# schematic.net
KiCad netlist of a schematic drawn in Altium Designer
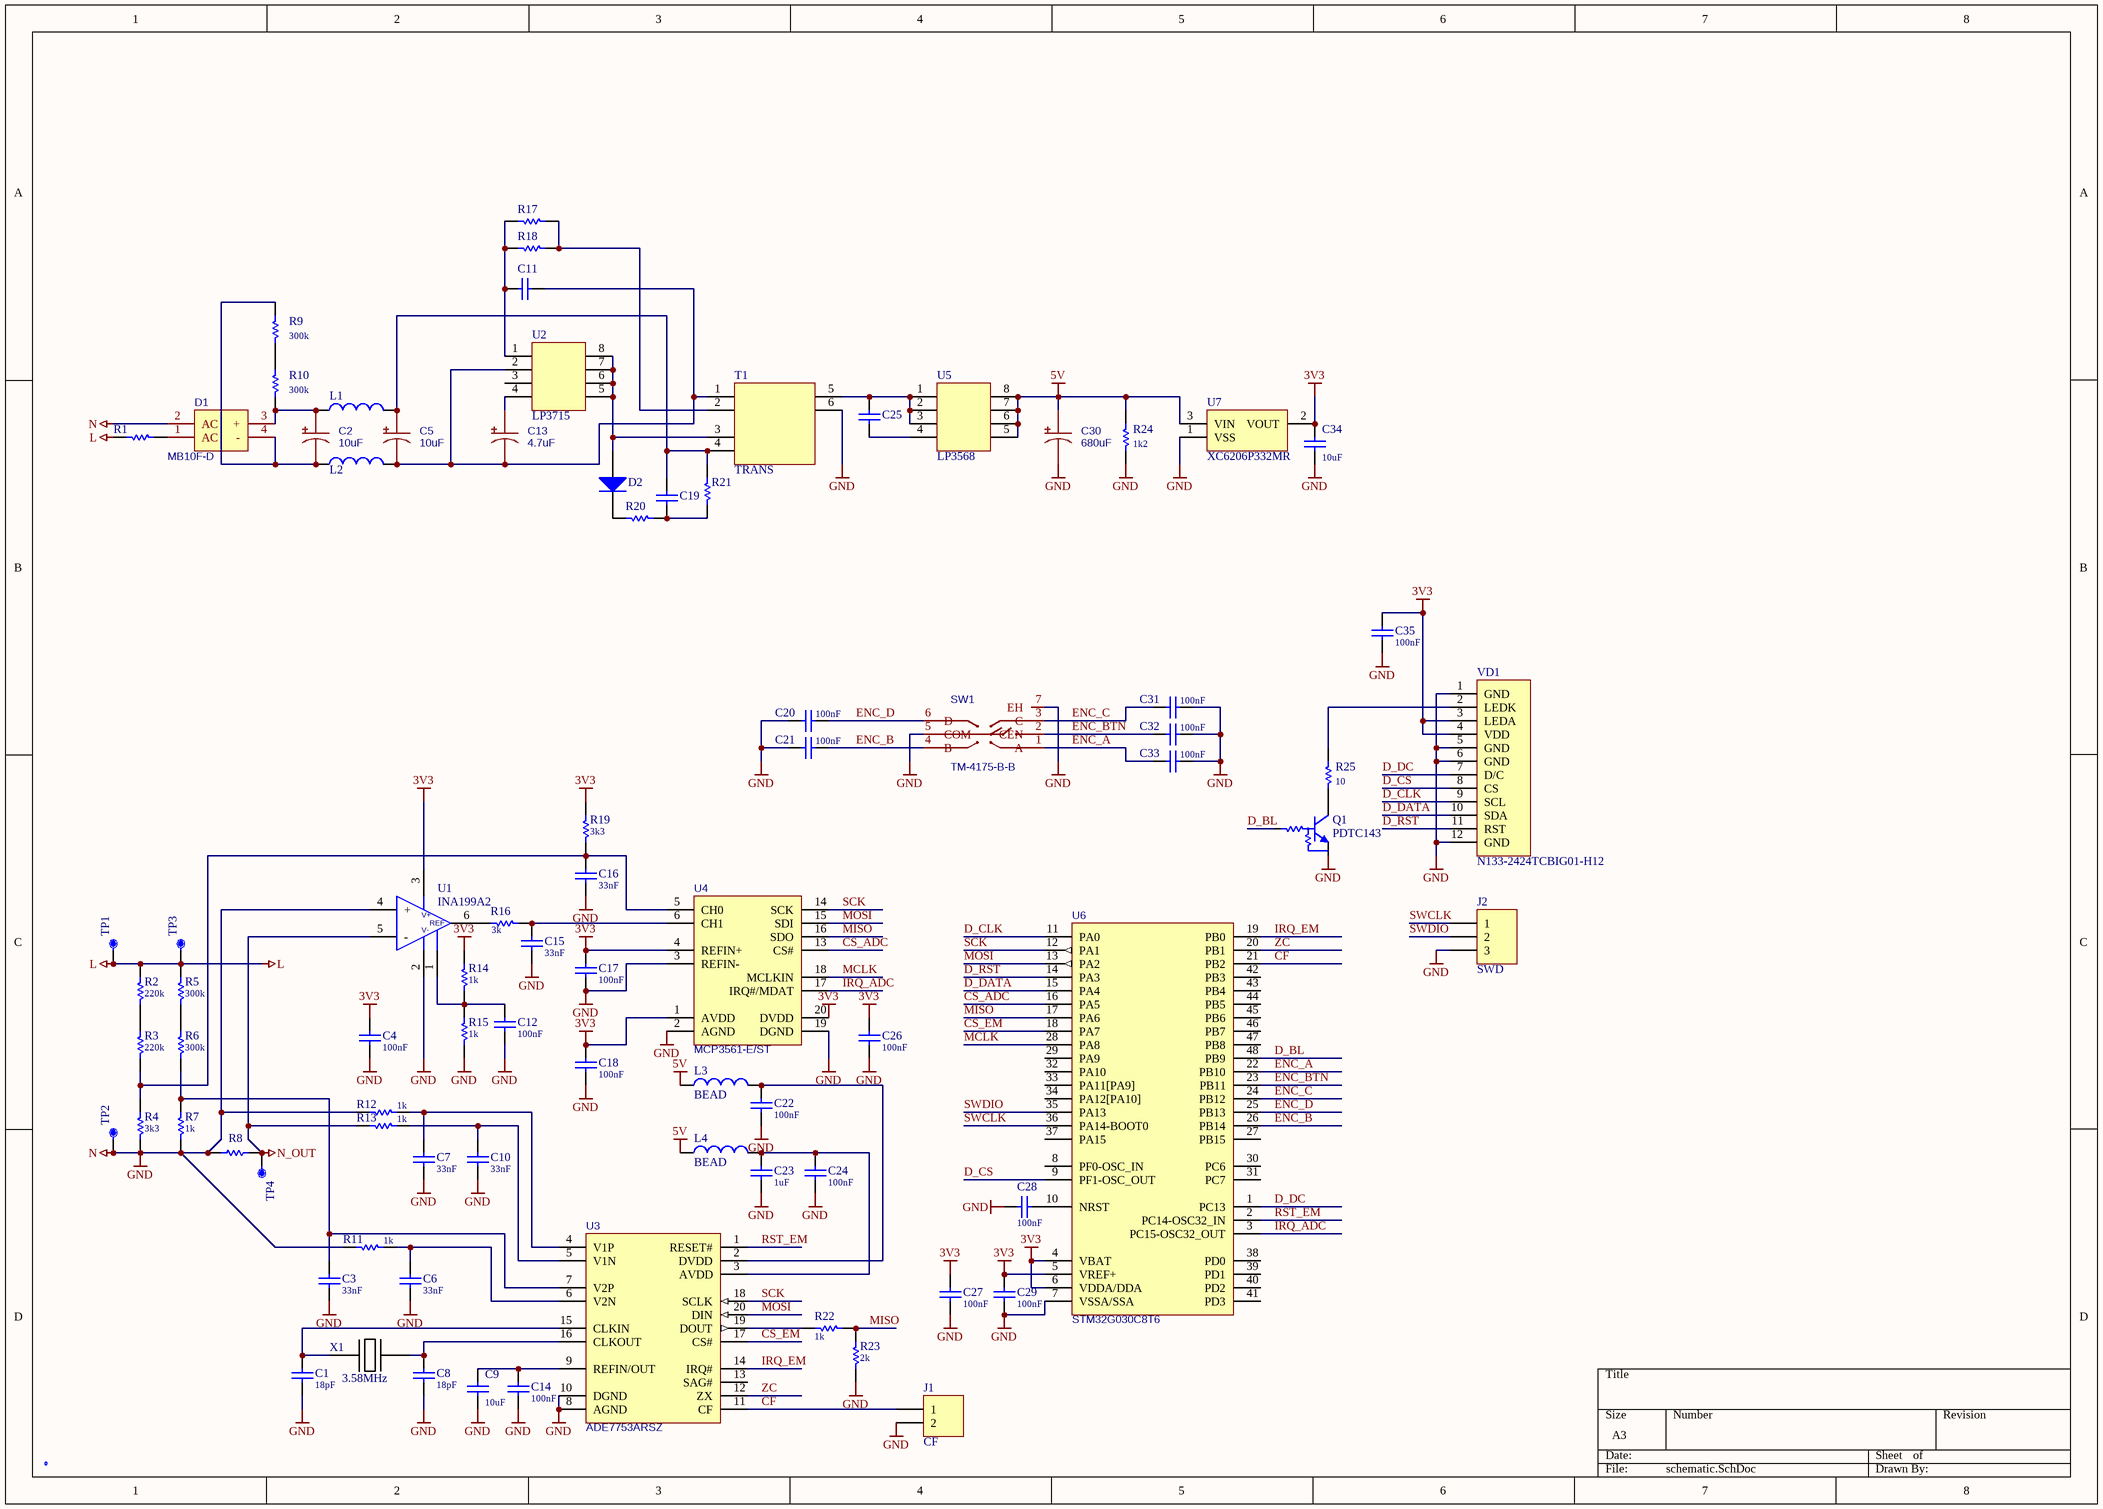
[diagram p0: schematic.SchDoc]

(export (version "E")
  (design (tool "Eeschema 10.0.6"))
  (components
    (comp (ref "C1")
      (value "18pF")
      (footprint "C0402")
      (fields (field (name "LCSC PART NUMBER") "C33149"))
      (libsource (lib "Miscellaneous Devices") (part "CAP"))
    )
    (comp (ref "C2")
      (value "10uF")
      (footprint "CAP-TH_BD8.0-P3.50-D0.6-FD_1")
      (description "01EC4138MHT10uF400V")
      (libsource (lib "altium-import") (part "root_0_220uF_"))
    )
    (comp (ref "C3")
      (value "33nF")
      (footprint "C0402")
      (libsource (lib "Miscellaneous Devices") (part "CAP"))
    )
    (comp (ref "C4")
      (value "100nF")
      (footprint "C0402")
      (libsource (lib "Miscellaneous Devices") (part "CAP"))
    )
    (comp (ref "C5")
      (value "10uF")
      (footprint "CAP-TH_BD8.0-P3.50-D0.6-FD_1")
      (description "01EC4138MHT10uF400V")
      (libsource (lib "altium-import") (part "root_0_220uF_"))
    )
    (comp (ref "C6")
      (value "33nF")
      (footprint "C0402")
      (libsource (lib "Miscellaneous Devices") (part "CAP"))
    )
    (comp (ref "C7")
      (value "33nF")
      (footprint "C0402")
      (fields (field (name "LCSC PART NUMBER") "C33149"))
      (libsource (lib "Miscellaneous Devices") (part "CAP"))
    )
    (comp (ref "C8")
      (value "18pF")
      (footprint "C0402")
      (fields (field (name "LCSC PART NUMBER") "C33149"))
      (libsource (lib "Miscellaneous Devices") (part "CAP"))
    )
    (comp (ref "C9")
      (value "10uF")
      (footprint "C1206")
      (libsource (lib "Miscellaneous Devices") (part "CAP"))
    )
    (comp (ref "C10")
      (value "33nF")
      (footprint "C0402")
      (fields (field (name "LCSC PART NUMBER") "C33149"))
      (libsource (lib "Miscellaneous Devices") (part "CAP"))
    )
    (comp (ref "C11") (value "~") (footprint "C0603") (libsource (lib "Miscellaneous Devices") (part "CAP")))
    (comp (ref "C12")
      (value "100nF")
      (footprint "C0402")
      (libsource (lib "Miscellaneous Devices") (part "CAP"))
    )
    (comp (ref "C13")
      (value "4.7uF")
      (footprint "CAP-TH_BD4.0-P2")
      (libsource (lib "altium-import") (part "root_0_220uF_"))
    )
    (comp (ref "C14")
      (value "100nF")
      (footprint "C0402")
      (libsource (lib "Miscellaneous Devices") (part "CAP"))
    )
    (comp (ref "C15")
      (value "33nF")
      (footprint "C0402")
      (libsource (lib "Miscellaneous Devices") (part "CAP"))
    )
    (comp (ref "C16")
      (value "33nF")
      (footprint "C0402")
      (libsource (lib "Miscellaneous Devices") (part "CAP"))
    )
    (comp (ref "C17")
      (value "100nF")
      (footprint "C0402")
      (libsource (lib "Miscellaneous Devices") (part "CAP"))
    )
    (comp (ref "C18")
      (value "100nF")
      (footprint "C0402")
      (libsource (lib "Miscellaneous Devices") (part "CAP"))
    )
    (comp (ref "C19") (value "~") (footprint "C1206") (libsource (lib "Miscellaneous Devices") (part "CAP")))
    (comp (ref "C20")
      (value "100nF")
      (footprint "C0402")
      (libsource (lib "Miscellaneous Devices") (part "CAP"))
    )
    (comp (ref "C21")
      (value "100nF")
      (footprint "C0402")
      (libsource (lib "Miscellaneous Devices") (part "CAP"))
    )
    (comp (ref "C22")
      (value "100nF")
      (footprint "C0402")
      (libsource (lib "Miscellaneous Devices") (part "CAP"))
    )
    (comp (ref "C23")
      (value "1uF")
      (footprint "C0603")
      (description "1uF 50V 0603")
      (fields (field (name "LCSC PART NUMBER") "C90540"))
      (libsource (lib "Miscellaneous Devices") (part "CAP"))
    )
    (comp (ref "C24")
      (value "100nF")
      (footprint "C0402")
      (libsource (lib "Miscellaneous Devices") (part "CAP"))
    )
    (comp (ref "C25") (value "~") (footprint "C0603") (libsource (lib "Miscellaneous Devices") (part "CAP")))
    (comp (ref "C26")
      (value "100nF")
      (footprint "C0402")
      (libsource (lib "Miscellaneous Devices") (part "CAP"))
    )
    (comp (ref "C27")
      (value "100nF")
      (footprint "C0402")
      (libsource (lib "Miscellaneous Devices") (part "CAP"))
    )
    (comp (ref "C28")
      (value "100nF")
      (footprint "C0603")
      (libsource (lib "Miscellaneous Devices") (part "CAP"))
    )
    (comp (ref "C29")
      (value "100nF")
      (footprint "C0402")
      (libsource (lib "Miscellaneous Devices") (part "CAP"))
    )
    (comp (ref "C30")
      (value "680uF")
      (footprint "CAP-TH_BD6.3-P2.54")
      (libsource (lib "altium-import") (part "root_0_220uF_"))
    )
    (comp (ref "C31")
      (value "100nF")
      (footprint "C0402")
      (libsource (lib "Miscellaneous Devices") (part "CAP"))
    )
    (comp (ref "C32")
      (value "100nF")
      (footprint "C0402")
      (libsource (lib "Miscellaneous Devices") (part "CAP"))
    )
    (comp (ref "C33")
      (value "100nF")
      (footprint "C0402")
      (libsource (lib "Miscellaneous Devices") (part "CAP"))
    )
    (comp (ref "C34")
      (value "10uF")
      (footprint "C1206")
      (libsource (lib "Miscellaneous Devices") (part "CAP"))
    )
    (comp (ref "C35")
      (value "100nF")
      (footprint "C0402")
      (libsource (lib "Miscellaneous Devices") (part "CAP"))
    )
    (comp (ref "D1")
      (value "MB10F-D")
      (footprint "MINIDIP_4P-L4.7-W3.8-P2.50-LS7.0-BL")
      (fields (field (name "LCSC PART NUMBER") "C908753"))
      (libsource (lib "Schlib1") (part "MB10F-D"))
    )
    (comp (ref "D2")
      (value "1N4148WS")
      (footprint "SOD-123")
      (libsource (lib "Miscellaneous Devices") (part "US1M-13-F"))
    )
    (comp (ref "J1") (value "CF") (footprint "HDR-1X2_2.54") (libsource (lib "Schlib1") (part "Header 2")))
    (comp (ref "J2")
      (value "SWD")
      (footprint "HDR-1X3_2.54")
      (libsource (lib "Miscellaneous Devices") (part "Header 3"))
    )
    (comp (ref "L1")
      (value "~")
      (footprint "IND_TH")
      (libsource (lib "Miscellaneous Devices") (part "BLM18AG601SN1D"))
    )
    (comp (ref "L2")
      (value "~")
      (footprint "L0805")
      (libsource (lib "Miscellaneous Devices") (part "BLM18AG601SN1D"))
    )
    (comp (ref "L3")
      (value "BEAD")
      (footprint "L0402")
      (description "BEAD 0402")
      (fields (field (name "LCSC PART NUMBER") "C92615"))
      (libsource (lib "") (part "BLM18AG601SN1D_1"))
    )
    (comp (ref "L4")
      (value "BEAD")
      (footprint "L0402")
      (description "BEAD 0402")
      (fields (field (name "LCSC PART NUMBER") "C92615"))
      (libsource (lib "") (part "BLM18AG601SN1D_1"))
    )
    (comp (ref "LOGO1") (value "LOGO") (footprint "LOGO") (libsource (lib "Schlib1") (part "LOGO")))
    (comp (ref "Q1")
      (value "PDTC143")
      (footprint "SOT-23")
      (description "PDTC143XT,215")
      (fields (field (name "LCSC PART NUMBER") "C183011"))
      (libsource (lib "Miscellaneous Devices") (part "MMBT2222ALT1G"))
    )
    (comp (ref "R1") (value "~") (footprint "IND_TH") (libsource (lib "Miscellaneous Devices") (part "RES")))
    (comp (ref "R2")
      (value "220k")
      (footprint "R1206")
      (libsource (lib "Miscellaneous Devices") (part "RES"))
    )
    (comp (ref "R3")
      (value "220k")
      (footprint "R1206")
      (libsource (lib "Miscellaneous Devices") (part "RES"))
    )
    (comp (ref "R4") (value "3k3") (footprint "R0603") (libsource (lib "Miscellaneous Devices") (part "RES")))
    (comp (ref "R5")
      (value "300k")
      (footprint "R1206")
      (libsource (lib "Miscellaneous Devices") (part "RES"))
    )
    (comp (ref "R6")
      (value "300k")
      (footprint "R1206")
      (libsource (lib "Miscellaneous Devices") (part "RES"))
    )
    (comp (ref "R7") (value "1k") (footprint "R0603") (libsource (lib "Miscellaneous Devices") (part "RES")))
    (comp (ref "R8")
      (value "~")
      (footprint "R2512-WIDE")
      (libsource (lib "Miscellaneous Devices") (part "RES"))
    )
    (comp (ref "R9")
      (value "300k")
      (footprint "R1206")
      (libsource (lib "Miscellaneous Devices") (part "RES"))
    )
    (comp (ref "R10")
      (value "300k")
      (footprint "R1206")
      (libsource (lib "Miscellaneous Devices") (part "RES"))
    )
    (comp (ref "R11") (value "1k") (footprint "R0603") (libsource (lib "Miscellaneous Devices") (part "RES")))
    (comp (ref "R12") (value "1k") (footprint "R0603") (libsource (lib "Miscellaneous Devices") (part "RES")))
    (comp (ref "R13") (value "1k") (footprint "R0603") (libsource (lib "Miscellaneous Devices") (part "RES")))
    (comp (ref "R14") (value "1k") (footprint "R0603") (libsource (lib "Miscellaneous Devices") (part "RES")))
    (comp (ref "R15") (value "1k") (footprint "R0603") (libsource (lib "Miscellaneous Devices") (part "RES")))
    (comp (ref "R16") (value "3k") (footprint "R0603") (libsource (lib "Miscellaneous Devices") (part "RES")))
    (comp (ref "R17") (value "~") (footprint "R0603") (libsource (lib "Miscellaneous Devices") (part "RES")))
    (comp (ref "R18") (value "~") (footprint "R0603") (libsource (lib "Miscellaneous Devices") (part "RES")))
    (comp (ref "R19")
      (value "3k3")
      (footprint "R0603")
      (libsource (lib "Miscellaneous Devices") (part "RES"))
    )
    (comp (ref "R20") (value "~") (footprint "R0805") (libsource (lib "Miscellaneous Devices") (part "RES")))
    (comp (ref "R21") (value "~") (footprint "R1206") (libsource (lib "Miscellaneous Devices") (part "RES")))
    (comp (ref "R22") (value "1k") (footprint "R0402") (libsource (lib "Miscellaneous Devices") (part "RES")))
    (comp (ref "R23") (value "2k") (footprint "R0402") (libsource (lib "Miscellaneous Devices") (part "RES")))
    (comp (ref "R24")
      (value "1k2")
      (footprint "R1206")
      (libsource (lib "Miscellaneous Devices") (part "RES"))
    )
    (comp (ref "R25") (value "10") (footprint "R0603") (libsource (lib "Miscellaneous Devices") (part "RES")))
    (comp (ref "SW1")
      (value "TM-4175-B-B")
      (footprint "SW-SMD_TM-4175-B-X")
      (fields (field (name "LCSC PART NUMBER") "C465996"))
      (libsource (lib "altium-import") (part "root_0_TM-4175-B-B_"))
    )
    (comp (ref "T1")
      (value "TRANS")
      (footprint "TRANSFORMER")
      (libsource (lib "Schlib1") (part "Component_2"))
    )
    (comp (ref "TP1")
      (value "~")
      (footprint "TP2030_SMD")
      (libsource (lib "Miscellaneous Devices") (part "TP_Dup1"))
    )
    (comp (ref "TP2")
      (value "~")
      (footprint "TP2030_SMD")
      (libsource (lib "Miscellaneous Devices") (part "TP_Dup1"))
    )
    (comp (ref "TP3")
      (value "~")
      (footprint "TP2030_SMD")
      (libsource (lib "Miscellaneous Devices") (part "TP_Dup1"))
    )
    (comp (ref "TP4")
      (value "~")
      (footprint "TP2030_SMD")
      (libsource (lib "Miscellaneous Devices") (part "TP_Dup1"))
    )
    (comp (ref "U1")
      (value "INA199A2")
      (footprint "SOT-363")
      (libsource (lib "Miscellaneous Devices") (part "MCP65R41T-2402"))
    )
    (comp (ref "U2") (value "LP3715") (footprint "SOIC-8") (libsource (lib "Schlib1") (part "Component_1")))
    (comp (ref "U3")
      (value "ADE7753ARSZ")
      (footprint "SSOP-20")
      (fields (field (name "LCSC PART NUMBER") "C654528"))
      (libsource (lib "Schlib1") (part "ADE7753ARSZ"))
    )
    (comp (ref "U4")
      (value "MCP3561-E/ST")
      (footprint "SSOP-20")
      (libsource (lib "Schlib1") (part "MCP3561-E/ST"))
    )
    (comp (ref "U5") (value "LP3568") (footprint "SOIC-8") (libsource (lib "Schlib1") (part "Component_1")))
    (comp (ref "U6")
      (value "STM32G030C8T6")
      (footprint "LQFP-48")
      (libsource (lib "Schlib1") (part "STM32G030C8T6"))
    )
    (comp (ref "U7")
      (value "XC6206P332MR")
      (footprint "SOT-23")
      (libsource (lib "Schlib1") (part "Component_4_1"))
    )
    (comp (ref "VD1")
      (value "N133-2424TCBIG01-H12")
      (footprint "LCD_PICO_1.3")
      (description "N133-2424TCBIG01-H12 19650 Waveshare")
      (libsource (lib "Schlib1") (part "Header 3"))
    )
    (comp (ref "X1")
      (value "3.58MHz")
      (footprint "HC-49S-SMD")
      (description "3.58MHz 20pF ±20ppm HC-49S")
      (libsource (lib "Schlib1") (part "CRYSTAL 12MHZ 3.20mm x 2.50mm"))
    )
  )
  (nets
    (net (code "1") (name "/CF") (class "Default")
      (node (ref "J1") (pin "1") (pinfunction "1_1") (pintype "passive"))
      (node (ref "U3") (pin "11") (pinfunction "CF_11") (pintype "passive"))
      (node (ref "U6") (pin "21") (pinfunction "PB2_21") (pintype "passive"))
    )
    (net (code "2") (name "/CS_ADC") (class "Default")
      (node (ref "U4") (pin "13") (pinfunction "CS#_13") (pintype "passive"))
      (node (ref "U6") (pin "16") (pinfunction "PA5_16") (pintype "passive"))
    )
    (net (code "3") (name "/CS_EM") (class "Default")
      (node (ref "U3") (pin "17") (pinfunction "CS#_17") (pintype "passive"))
      (node (ref "U6") (pin "18") (pinfunction "PA7_18") (pintype "passive"))
    )
    (net (code "4") (name "/D_BL") (class "Default")
      (node (ref "Q1") (pin "1") (pinfunction "B_1") (pintype "passive"))
      (node (ref "U6") (pin "48") (pinfunction "PB9_48") (pintype "passive"))
    )
    (net (code "5") (name "/D_CLK") (class "Default")
      (node (ref "U6") (pin "11") (pinfunction "PA0_11") (pintype "passive"))
      (node (ref "VD1") (pin "9") (pinfunction "SCL_9") (pintype "passive"))
    )
    (net (code "6") (name "/D_CS") (class "Default")
      (node (ref "U6") (pin "9") (pinfunction "PF1-OSC_OUT_9") (pintype "passive"))
      (node (ref "VD1") (pin "8") (pinfunction "CS_8") (pintype "passive"))
    )
    (net (code "7") (name "/D_DATA") (class "Default")
      (node (ref "U6") (pin "15") (pinfunction "PA4_15") (pintype "passive"))
      (node (ref "VD1") (pin "10") (pinfunction "SDA_10") (pintype "passive"))
    )
    (net (code "8") (name "/D_DC") (class "Default")
      (node (ref "U6") (pin "1") (pinfunction "PC13_1") (pintype "passive"))
      (node (ref "VD1") (pin "7") (pinfunction "D/C_7") (pintype "passive"))
    )
    (net (code "9") (name "/D_RST") (class "Default")
      (node (ref "U6") (pin "14") (pinfunction "PA3_14") (pintype "passive"))
      (node (ref "VD1") (pin "11") (pinfunction "RST_11") (pintype "passive"))
    )
    (net (code "10") (name "/ENC_A") (class "Default")
      (node (ref "C33") (pin "2") (pinfunction "2_2") (pintype "passive"))
      (node (ref "SW1") (pin "1") (pinfunction "A_1") (pintype "passive"))
      (node (ref "U6") (pin "22") (pinfunction "PB10_22") (pintype "passive"))
    )
    (net (code "11") (name "/ENC_B") (class "Default")
      (node (ref "C21") (pin "1") (pinfunction "1_1") (pintype "passive"))
      (node (ref "SW1") (pin "4") (pinfunction "B_4") (pintype "passive"))
      (node (ref "U6") (pin "26") (pinfunction "PB14_26") (pintype "passive"))
    )
    (net (code "12") (name "/ENC_BTN") (class "Default")
      (node (ref "C32") (pin "2") (pinfunction "2_2") (pintype "passive"))
      (node (ref "SW1") (pin "2") (pinfunction "CEN_2") (pintype "passive"))
      (node (ref "U6") (pin "23") (pinfunction "PB11_23") (pintype "passive"))
    )
    (net (code "13") (name "/ENC_C") (class "Default")
      (node (ref "C31") (pin "2") (pinfunction "2_2") (pintype "passive"))
      (node (ref "SW1") (pin "3") (pinfunction "C_3") (pintype "passive"))
      (node (ref "U6") (pin "24") (pinfunction "PB12_24") (pintype "passive"))
    )
    (net (code "14") (name "/ENC_D") (class "Default")
      (node (ref "C20") (pin "1") (pinfunction "1_1") (pintype "passive"))
      (node (ref "SW1") (pin "6") (pinfunction "D_6") (pintype "passive"))
      (node (ref "U6") (pin "25") (pinfunction "PB13_25") (pintype "passive"))
    )
    (net (code "15") (name "/IRQ_ADC") (class "Default")
      (node (ref "U4") (pin "17") (pinfunction "IRQ#/MDAT_17") (pintype "passive"))
      (node (ref "U6") (pin "3") (pinfunction "PC15-OSC32_OUT_3") (pintype "passive"))
    )
    (net (code "16") (name "/IRQ_EM") (class "Default")
      (node (ref "U3") (pin "14") (pinfunction "IRQ#_14") (pintype "passive"))
      (node (ref "U6") (pin "19") (pinfunction "PB0_19") (pintype "passive"))
    )
    (net (code "17") (name "/MCLK") (class "Default")
      (node (ref "U4") (pin "18") (pinfunction "MCLKIN_18") (pintype "passive"))
      (node (ref "U6") (pin "28") (pinfunction "PA8_28") (pintype "passive"))
    )
    (net (code "18") (name "/MISO") (class "Default")
      (node (ref "R22") (pin "1") (pinfunction "1_1") (pintype "passive"))
      (node (ref "R23") (pin "1") (pinfunction "1_1") (pintype "passive"))
      (node (ref "U4") (pin "16") (pinfunction "SDO_16") (pintype "passive"))
      (node (ref "U6") (pin "17") (pinfunction "PA6_17") (pintype "passive"))
    )
    (net (code "19") (name "/MOSI") (class "Default")
      (node (ref "U3") (pin "20") (pinfunction "DIN_20") (pintype "input"))
      (node (ref "U4") (pin "15") (pinfunction "SDI_15") (pintype "passive"))
      (node (ref "U6") (pin "13") (pinfunction "PA2_13") (pintype "output"))
    )
    (net (code "20") (name "/RST_EM") (class "Default")
      (node (ref "U3") (pin "1") (pinfunction "RESET#_1") (pintype "passive"))
      (node (ref "U6") (pin "2") (pinfunction "PC14-OSC32_IN_2") (pintype "passive"))
    )
    (net (code "21") (name "/SCK") (class "Default")
      (node (ref "U3") (pin "18") (pinfunction "SCLK_18") (pintype "input"))
      (node (ref "U4") (pin "14") (pinfunction "SCK_14") (pintype "passive"))
      (node (ref "U6") (pin "12") (pinfunction "PA1_12") (pintype "output"))
    )
    (net (code "22") (name "/SWCLK") (class "Default")
      (node (ref "J2") (pin "1") (pinfunction "1_1") (pintype "passive"))
      (node (ref "U6") (pin "36") (pinfunction "PA14-BOOT0_36") (pintype "passive"))
    )
    (net (code "23") (name "/SWDIO") (class "Default")
      (node (ref "J2") (pin "2") (pinfunction "2_2") (pintype "passive"))
      (node (ref "U6") (pin "35") (pinfunction "PA13_35") (pintype "passive"))
    )
    (net (code "24") (name "/ZC") (class "Default")
      (node (ref "U3") (pin "12") (pinfunction "ZX_12") (pintype "passive"))
      (node (ref "U6") (pin "20") (pinfunction "PB1_20") (pintype "passive"))
    )
    (net (code "25") (name "3V3") (class "Default")
      (node (ref "C17") (pin "2") (pinfunction "2_2") (pintype "passive"))
      (node (ref "C18") (pin "2") (pinfunction "2_2") (pintype "passive"))
      (node (ref "C26") (pin "2") (pinfunction "2_2") (pintype "passive"))
      (node (ref "C27") (pin "2") (pinfunction "2_2") (pintype "passive"))
      (node (ref "C29") (pin "2") (pinfunction "2_2") (pintype "passive"))
      (node (ref "C34") (pin "2") (pinfunction "2_2") (pintype "passive"))
      (node (ref "C35") (pin "2") (pinfunction "2_2") (pintype "passive"))
      (node (ref "C4") (pin "2") (pinfunction "2_2") (pintype "passive"))
      (node (ref "R14") (pin "2") (pinfunction "2_2") (pintype "passive"))
      (node (ref "R19") (pin "1") (pinfunction "1_1") (pintype "passive"))
      (node (ref "U1") (pin "3") (pinfunction "V+_3") (pintype "passive"))
      (node (ref "U4") (pin "1") (pinfunction "AVDD_1") (pintype "passive"))
      (node (ref "U4") (pin "20") (pinfunction "DVDD_20") (pintype "passive"))
      (node (ref "U4") (pin "4") (pinfunction "REFIN+_4") (pintype "passive"))
      (node (ref "U6") (pin "4") (pinfunction "VBAT_4") (pintype "passive"))
      (node (ref "U6") (pin "5") (pinfunction "VREF+_5") (pintype "passive"))
      (node (ref "U6") (pin "6") (pinfunction "VDDA/DDA_6") (pintype "passive"))
      (node (ref "U7") (pin "2") (pinfunction "VOUT_2") (pintype "passive"))
      (node (ref "VD1") (pin "3") (pinfunction "LEDA_3") (pintype "passive"))
      (node (ref "VD1") (pin "4") (pinfunction "VDD_4") (pintype "passive"))
    )
    (net (code "26") (name "5V") (class "Default")
      (node (ref "C30") (pin "1") (pinfunction "1_1") (pintype "passive"))
      (node (ref "L3") (pin "1") (pinfunction "1_1") (pintype "passive"))
      (node (ref "L4") (pin "1") (pinfunction "1_1") (pintype "passive"))
      (node (ref "R24") (pin "2") (pinfunction "2_2") (pintype "passive"))
      (node (ref "U5") (pin "5") (pintype "passive"))
      (node (ref "U5") (pin "6") (pintype "passive"))
      (node (ref "U5") (pin "7") (pintype "passive"))
      (node (ref "U5") (pin "8") (pintype "passive"))
      (node (ref "U7") (pin "3") (pinfunction "VIN_3") (pintype "passive"))
    )
    (net (code "27") (name "GND") (class "Default")
      (node (ref "C1") (pin "1") (pinfunction "1_1") (pintype "passive"))
      (node (ref "C10") (pin "1") (pinfunction "1_1") (pintype "passive"))
      (node (ref "C12") (pin "1") (pinfunction "1_1") (pintype "passive"))
      (node (ref "C14") (pin "1") (pinfunction "1_1") (pintype "passive"))
      (node (ref "C15") (pin "1") (pinfunction "1_1") (pintype "passive"))
      (node (ref "C16") (pin "1") (pinfunction "1_1") (pintype "passive"))
      (node (ref "C17") (pin "1") (pinfunction "1_1") (pintype "passive"))
      (node (ref "C18") (pin "1") (pinfunction "1_1") (pintype "passive"))
      (node (ref "C20") (pin "2") (pinfunction "2_2") (pintype "passive"))
      (node (ref "C21") (pin "2") (pinfunction "2_2") (pintype "passive"))
      (node (ref "C22") (pin "1") (pinfunction "1_1") (pintype "passive"))
      (node (ref "C23") (pin "1") (pinfunction "1_1") (pintype "passive"))
      (node (ref "C24") (pin "2") (pinfunction "2_2") (pintype "passive"))
      (node (ref "C26") (pin "1") (pinfunction "1_1") (pintype "passive"))
      (node (ref "C27") (pin "1") (pinfunction "1_1") (pintype "passive"))
      (node (ref "C28") (pin "2") (pinfunction "2_2") (pintype "passive"))
      (node (ref "C29") (pin "1") (pinfunction "1_1") (pintype "passive"))
      (node (ref "C3") (pin "1") (pinfunction "1_1") (pintype "passive"))
      (node (ref "C30") (pin "2") (pinfunction "2_2") (pintype "passive"))
      (node (ref "C31") (pin "1") (pinfunction "1_1") (pintype "passive"))
      (node (ref "C32") (pin "1") (pinfunction "1_1") (pintype "passive"))
      (node (ref "C33") (pin "1") (pinfunction "1_1") (pintype "passive"))
      (node (ref "C34") (pin "1") (pinfunction "1_1") (pintype "passive"))
      (node (ref "C35") (pin "1") (pinfunction "1_1") (pintype "passive"))
      (node (ref "C4") (pin "1") (pinfunction "1_1") (pintype "passive"))
      (node (ref "C6") (pin "1") (pinfunction "1_1") (pintype "passive"))
      (node (ref "C7") (pin "1") (pinfunction "1_1") (pintype "passive"))
      (node (ref "C8") (pin "1") (pinfunction "1_1") (pintype "passive"))
      (node (ref "C9") (pin "1") (pinfunction "1_1") (pintype "passive"))
      (node (ref "D1") (pin "2") (pinfunction "AC_2") (pintype "passive"))
      (node (ref "J1") (pin "2") (pinfunction "2_2") (pintype "passive"))
      (node (ref "J2") (pin "3") (pinfunction "3_3") (pintype "passive"))
      (node (ref "Q1") (pin "2") (pinfunction "E_2") (pintype "passive"))
      (node (ref "R11") (pin "2") (pinfunction "2_2") (pintype "passive"))
      (node (ref "R12") (pin "2") (pinfunction "2_2") (pintype "passive"))
      (node (ref "R15") (pin "1") (pinfunction "1_1") (pintype "passive"))
      (node (ref "R23") (pin "2") (pinfunction "2_2") (pintype "passive"))
      (node (ref "R24") (pin "1") (pinfunction "1_1") (pintype "passive"))
      (node (ref "R4") (pin "2") (pinfunction "2_2") (pintype "passive"))
      (node (ref "R7") (pin "2") (pinfunction "2_2") (pintype "passive"))
      (node (ref "R8") (pin "2") (pinfunction "2_2") (pintype "passive"))
      (node (ref "SW1") (pin "5") (pinfunction "COM_5") (pintype "passive"))
      (node (ref "SW1") (pin "7") (pinfunction "EH_7") (pintype "passive"))
      (node (ref "T1") (pin "6") (pintype "passive"))
      (node (ref "TP2") (pin "1") (pinfunction "1_1") (pintype "passive"))
      (node (ref "U1") (pin "2") (pinfunction "GND_2") (pintype "power_in"))
      (node (ref "U1") (pin "4") (pinfunction "+_4") (pintype "passive"))
      (node (ref "U3") (pin "10") (pinfunction "DGND_10") (pintype "passive"))
      (node (ref "U3") (pin "8") (pinfunction "AGND_8") (pintype "passive"))
      (node (ref "U4") (pin "19") (pinfunction "DGND_19") (pintype "passive"))
      (node (ref "U4") (pin "2") (pinfunction "AGND_2") (pintype "passive"))
      (node (ref "U4") (pin "3") (pinfunction "REFIN-_3") (pintype "passive"))
      (node (ref "U6") (pin "7") (pinfunction "VSSA/SSA_7") (pintype "passive"))
      (node (ref "U7") (pin "1") (pinfunction "VSS_1") (pintype "passive"))
      (node (ref "VD1") (pin "1") (pinfunction "GND_1") (pintype "passive"))
      (node (ref "VD1") (pin "12") (pinfunction "GND_12") (pintype "passive"))
      (node (ref "VD1") (pin "5") (pinfunction "GND_5") (pintype "passive"))
      (node (ref "VD1") (pin "6") (pinfunction "GND_6") (pintype "passive"))
    )
    (net (code "28") (name "L") (class "Default")
      (node (ref "R1") (pin "2") (pinfunction "2_2") (pintype "passive"))
      (node (ref "R2") (pin "1") (pinfunction "1_1") (pintype "passive"))
      (node (ref "R5") (pin "1") (pinfunction "1_1") (pintype "passive"))
      (node (ref "TP1") (pin "1") (pinfunction "1_1") (pintype "passive"))
      (node (ref "TP3") (pin "1") (pinfunction "1_1") (pintype "passive"))
    )
    (net (code "29") (name "N_OUT") (class "Default")
      (node (ref "R13") (pin "2") (pinfunction "2_2") (pintype "passive"))
      (node (ref "R8") (pin "1") (pinfunction "1_1") (pintype "passive"))
      (node (ref "TP4") (pin "1") (pinfunction "1_1") (pintype "passive"))
      (node (ref "U1") (pin "5") (pinfunction "-_5") (pintype "passive"))
    )
    (net (code "30") (name "Net-(C11-Pad1)") (class "Default")
      (node (ref "C11") (pin "1") (pinfunction "1_1") (pintype "passive"))
      (node (ref "C13") (pin "2") (pinfunction "2_2") (pintype "passive"))
      (node (ref "C5") (pin "2") (pinfunction "2_2") (pintype "passive"))
      (node (ref "L2") (pin "1") (pinfunction "1_1") (pintype "passive"))
      (node (ref "T1") (pin "1") (pintype "passive"))
      (node (ref "U2") (pin "2") (pintype "passive"))
    )
    (net (code "31") (name "Net-(C11-Pad2)") (class "Default")
      (node (ref "C11") (pin "2") (pinfunction "2_2") (pintype "passive"))
      (node (ref "R17") (pin "2") (pinfunction "2_2") (pintype "passive"))
      (node (ref "R18") (pin "2") (pinfunction "2_2") (pintype "passive"))
      (node (ref "U2") (pin "1") (pintype "passive"))
    )
    (net (code "32") (name "Net-(C13-Pad1)") (class "Default")
      (node (ref "C13") (pin "1") (pinfunction "1_1") (pintype "passive"))
      (node (ref "U2") (pin "4") (pintype "passive"))
    )
    (net (code "33") (name "Net-(C19-Pad1)") (class "Default")
      (node (ref "C19") (pin "1") (pinfunction "1_1") (pintype "passive"))
      (node (ref "C5") (pin "1") (pinfunction "1_1") (pintype "passive"))
      (node (ref "L1") (pin "1") (pinfunction "1_1") (pintype "passive"))
      (node (ref "R21") (pin "2") (pinfunction "2_2") (pintype "passive"))
      (node (ref "T1") (pin "4") (pintype "passive"))
    )
    (net (code "34") (name "Net-(C19-Pad2)") (class "Default")
      (node (ref "C19") (pin "2") (pinfunction "2_2") (pintype "passive"))
      (node (ref "R20") (pin "2") (pinfunction "2_2") (pintype "passive"))
      (node (ref "R21") (pin "1") (pinfunction "1_1") (pintype "passive"))
    )
    (net (code "35") (name "Net-(C25-Pad1)") (class "Default")
      (node (ref "C25") (pin "1") (pinfunction "1_1") (pintype "passive"))
      (node (ref "U5") (pin "4") (pintype "passive"))
    )
    (net (code "36") (name "Net-(C25-Pad2)") (class "Default")
      (node (ref "C25") (pin "2") (pinfunction "2_2") (pintype "passive"))
      (node (ref "T1") (pin "5") (pintype "passive"))
      (node (ref "U5") (pin "1") (pintype "passive"))
      (node (ref "U5") (pin "2") (pintype "passive"))
      (node (ref "U5") (pin "3") (pintype "passive"))
    )
    (net (code "37") (name "Net-(D1-+)") (class "Default")
      (node (ref "C2") (pin "1") (pinfunction "1_1") (pintype "passive"))
      (node (ref "D1") (pin "3") (pinfunction "+_3") (pintype "passive"))
      (node (ref "L1") (pin "2") (pinfunction "2_2") (pintype "passive"))
      (node (ref "R10") (pin "1") (pinfunction "1_1") (pintype "passive"))
    )
    (net (code "38") (name "Net-(D1--)") (class "Default")
      (node (ref "C2") (pin "2") (pinfunction "2_2") (pintype "passive"))
      (node (ref "D1") (pin "4") (pinfunction "-_4") (pintype "passive"))
      (node (ref "L2") (pin "2") (pinfunction "2_2") (pintype "passive"))
      (node (ref "R9") (pin "2") (pinfunction "2_2") (pintype "passive"))
    )
    (net (code "39") (name "Net-(D1-AC-Pad1)") (class "Default")
      (node (ref "D1") (pin "1") (pinfunction "AC_1") (pintype "passive"))
      (node (ref "R1") (pin "1") (pinfunction "1_1") (pintype "passive"))
    )
    (net (code "40") (name "Net-(D2-A)") (class "Default")
      (node (ref "D2") (pin "1") (pinfunction "A_1") (pintype "passive"))
      (node (ref "T1") (pin "3") (pintype "passive"))
      (node (ref "U2") (pin "5") (pintype "passive"))
      (node (ref "U2") (pin "6") (pintype "passive"))
      (node (ref "U2") (pin "7") (pintype "passive"))
      (node (ref "U2") (pin "8") (pintype "passive"))
    )
    (net (code "41") (name "Net-(D2-K)") (class "Default")
      (node (ref "D2") (pin "2") (pinfunction "K_2") (pintype "passive"))
      (node (ref "R20") (pin "1") (pinfunction "1_1") (pintype "passive"))
    )
    (net (code "42") (name "Net-(Q1-C)") (class "Default")
      (node (ref "Q1") (pin "3") (pinfunction "C_3") (pintype "passive"))
      (node (ref "R25") (pin "2") (pinfunction "2_2") (pintype "passive"))
    )
    (net (code "43") (name "Net-(R2-Pad2)") (class "Default")
      (node (ref "R2") (pin "2") (pinfunction "2_2") (pintype "passive"))
      (node (ref "R3") (pin "1") (pinfunction "1_1") (pintype "passive"))
    )
    (net (code "44") (name "Net-(R5-Pad2)") (class "Default")
      (node (ref "R5") (pin "2") (pinfunction "2_2") (pintype "passive"))
      (node (ref "R6") (pin "1") (pinfunction "1_1") (pintype "passive"))
    )
    (net (code "45") (name "Net-(R10-Pad2)") (class "Default")
      (node (ref "R10") (pin "2") (pinfunction "2_2") (pintype "passive"))
      (node (ref "R9") (pin "1") (pinfunction "1_1") (pintype "passive"))
    )
    (net (code "46") (name "Net-(R17-Pad1)") (class "Default")
      (node (ref "R17") (pin "1") (pinfunction "1_1") (pintype "passive"))
      (node (ref "R18") (pin "1") (pinfunction "1_1") (pintype "passive"))
      (node (ref "T1") (pin "2") (pintype "passive"))
    )
    (net (code "47") (name "Net-(U1-OUT)") (class "Default")
      (node (ref "R16") (pin "2") (pinfunction "2_2") (pintype "passive"))
      (node (ref "U1") (pin "6") (pinfunction "OUT_6") (pintype "passive"))
    )
    (net (code "48") (name "Net-(U1-REF)") (class "Default")
      (node (ref "C12") (pin "2") (pinfunction "2_2") (pintype "passive"))
      (node (ref "R14") (pin "1") (pinfunction "1_1") (pintype "passive"))
      (node (ref "R15") (pin "2") (pinfunction "2_2") (pintype "passive"))
      (node (ref "U1") (pin "1") (pinfunction "REF_1") (pintype "power_in"))
    )
    (net (code "49") (name "Net-(U3-AVDD)") (class "Default")
      (node (ref "C23") (pin "2") (pinfunction "2_2") (pintype "passive"))
      (node (ref "C24") (pin "1") (pinfunction "1_1") (pintype "passive"))
      (node (ref "L4") (pin "2") (pinfunction "2_2") (pintype "passive"))
      (node (ref "U3") (pin "3") (pinfunction "AVDD_3") (pintype "passive"))
    )
    (net (code "50") (name "Net-(U3-CLKIN)") (class "Default")
      (node (ref "C1") (pin "2") (pinfunction "2_2") (pintype "passive"))
      (node (ref "U3") (pin "15") (pinfunction "CLKIN_15") (pintype "passive"))
      (node (ref "X1") (pin "1") (pinfunction "X1_1") (pintype "passive"))
    )
    (net (code "51") (name "Net-(U3-CLKOUT)") (class "Default")
      (node (ref "C8") (pin "2") (pinfunction "2_2") (pintype "passive"))
      (node (ref "U3") (pin "16") (pinfunction "CLKOUT_16") (pintype "passive"))
      (node (ref "X1") (pin "2") (pinfunction "X2_2") (pintype "passive"))
    )
    (net (code "52") (name "Net-(U3-DOUT)") (class "Default")
      (node (ref "R22") (pin "2") (pinfunction "2_2") (pintype "passive"))
      (node (ref "U3") (pin "19") (pinfunction "DOUT_19") (pintype "output"))
    )
    (net (code "53") (name "Net-(U3-DVDD)") (class "Default")
      (node (ref "C22") (pin "2") (pinfunction "2_2") (pintype "passive"))
      (node (ref "L3") (pin "2") (pinfunction "2_2") (pintype "passive"))
      (node (ref "U3") (pin "2") (pinfunction "DVDD_2") (pintype "passive"))
    )
    (net (code "54") (name "Net-(U3-REFIN{slash}OUT)") (class "Default")
      (node (ref "C14") (pin "2") (pinfunction "2_2") (pintype "passive"))
      (node (ref "C9") (pin "2") (pinfunction "2_2") (pintype "passive"))
      (node (ref "U3") (pin "9") (pinfunction "REFIN/OUT_9") (pintype "passive"))
    )
    (net (code "55") (name "Net-(U3-V1N)") (class "Default")
      (node (ref "C10") (pin "2") (pinfunction "2_2") (pintype "passive"))
      (node (ref "R13") (pin "1") (pinfunction "1_1") (pintype "passive"))
      (node (ref "U3") (pin "5") (pinfunction "V1N_5") (pintype "passive"))
    )
    (net (code "56") (name "Net-(U3-V1P)") (class "Default")
      (node (ref "C7") (pin "2") (pinfunction "2_2") (pintype "passive"))
      (node (ref "R12") (pin "1") (pinfunction "1_1") (pintype "passive"))
      (node (ref "U3") (pin "4") (pinfunction "V1P_4") (pintype "passive"))
    )
    (net (code "57") (name "Net-(U3-V2N)") (class "Default")
      (node (ref "C6") (pin "2") (pinfunction "2_2") (pintype "passive"))
      (node (ref "R11") (pin "1") (pinfunction "1_1") (pintype "passive"))
      (node (ref "U3") (pin "6") (pinfunction "V2N_6") (pintype "passive"))
    )
    (net (code "58") (name "Net-(U3-V2P)") (class "Default")
      (node (ref "C3") (pin "2") (pinfunction "2_2") (pintype "passive"))
      (node (ref "R6") (pin "2") (pinfunction "2_2") (pintype "passive"))
      (node (ref "R7") (pin "1") (pinfunction "1_1") (pintype "passive"))
      (node (ref "U3") (pin "7") (pinfunction "V2P_7") (pintype "passive"))
    )
    (net (code "59") (name "Net-(U4-CH0)") (class "Default")
      (node (ref "C16") (pin "2") (pinfunction "2_2") (pintype "passive"))
      (node (ref "R19") (pin "2") (pinfunction "2_2") (pintype "passive"))
      (node (ref "R3") (pin "2") (pinfunction "2_2") (pintype "passive"))
      (node (ref "R4") (pin "1") (pinfunction "1_1") (pintype "passive"))
      (node (ref "U4") (pin "5") (pinfunction "CH0_5") (pintype "passive"))
    )
    (net (code "60") (name "Net-(U4-CH1)") (class "Default")
      (node (ref "C15") (pin "2") (pinfunction "2_2") (pintype "passive"))
      (node (ref "R16") (pin "1") (pinfunction "1_1") (pintype "passive"))
      (node (ref "U4") (pin "6") (pinfunction "CH1_6") (pintype "passive"))
    )
    (net (code "61") (name "Net-(U6-NRST)") (class "Default")
      (node (ref "C28") (pin "1") (pinfunction "1_1") (pintype "passive"))
      (node (ref "U6") (pin "10") (pinfunction "NRST_10") (pintype "passive"))
    )
    (net (code "62") (name "Net-(VD1-LEDK)") (class "Default")
      (node (ref "R25") (pin "1") (pinfunction "1_1") (pintype "passive"))
      (node (ref "VD1") (pin "2") (pinfunction "LEDK_2") (pintype "passive"))
    )
    (net (code "63") (name "unconnected-(U2-Pad3)") (class "Default")
      (node (ref "U2") (pin "3") (pintype "passive"))
    )
    (net (code "64") (name "unconnected-(U3-SAG#-Pad13)") (class "Default")
      (node (ref "U3") (pin "13") (pinfunction "SAG#_13") (pintype "passive"))
    )
    (net (code "65") (name "unconnected-(U6-PA9-Pad29)") (class "Default")
      (node (ref "U6") (pin "29") (pinfunction "PA9_29") (pintype "passive"))
    )
    (net (code "66") (name "unconnected-(U6-PA10-Pad32)") (class "Default")
      (node (ref "U6") (pin "32") (pinfunction "PA10_32") (pintype "passive"))
    )
    (net (code "67") (name "unconnected-(U6-PA11[PA9]-Pad33)") (class "Default")
      (node (ref "U6") (pin "33") (pinfunction "PA11[PA9]_33") (pintype "passive"))
    )
    (net (code "68") (name "unconnected-(U6-PA12[PA10]-Pad34)") (class "Default")
      (node (ref "U6") (pin "34") (pinfunction "PA12[PA10]_34") (pintype "passive"))
    )
    (net (code "69") (name "unconnected-(U6-PA15-Pad37)") (class "Default")
      (node (ref "U6") (pin "37") (pinfunction "PA15_37") (pintype "passive"))
    )
    (net (code "70") (name "unconnected-(U6-PB3-Pad42)") (class "Default")
      (node (ref "U6") (pin "42") (pinfunction "PB3_42") (pintype "passive"))
    )
    (net (code "71") (name "unconnected-(U6-PB4-Pad43)") (class "Default")
      (node (ref "U6") (pin "43") (pinfunction "PB4_43") (pintype "passive"))
    )
    (net (code "72") (name "unconnected-(U6-PB5-Pad44)") (class "Default")
      (node (ref "U6") (pin "44") (pinfunction "PB5_44") (pintype "passive"))
    )
    (net (code "73") (name "unconnected-(U6-PB6-Pad45)") (class "Default")
      (node (ref "U6") (pin "45") (pinfunction "PB6_45") (pintype "passive"))
    )
    (net (code "74") (name "unconnected-(U6-PB7-Pad46)") (class "Default")
      (node (ref "U6") (pin "46") (pinfunction "PB7_46") (pintype "passive"))
    )
    (net (code "75") (name "unconnected-(U6-PB8-Pad47)") (class "Default")
      (node (ref "U6") (pin "47") (pinfunction "PB8_47") (pintype "passive"))
    )
    (net (code "76") (name "unconnected-(U6-PB15-Pad27)") (class "Default")
      (node (ref "U6") (pin "27") (pinfunction "PB15_27") (pintype "passive"))
    )
    (net (code "77") (name "unconnected-(U6-PC6-Pad30)") (class "Default")
      (node (ref "U6") (pin "30") (pinfunction "PC6_30") (pintype "passive"))
    )
    (net (code "78") (name "unconnected-(U6-PC7-Pad31)") (class "Default")
      (node (ref "U6") (pin "31") (pinfunction "PC7_31") (pintype "passive"))
    )
    (net (code "79") (name "unconnected-(U6-PD0-Pad38)") (class "Default")
      (node (ref "U6") (pin "38") (pinfunction "PD0_38") (pintype "passive"))
    )
    (net (code "80") (name "unconnected-(U6-PD1-Pad39)") (class "Default")
      (node (ref "U6") (pin "39") (pinfunction "PD1_39") (pintype "passive"))
    )
    (net (code "81") (name "unconnected-(U6-PD2-Pad40)") (class "Default")
      (node (ref "U6") (pin "40") (pinfunction "PD2_40") (pintype "passive"))
    )
    (net (code "82") (name "unconnected-(U6-PD3-Pad41)") (class "Default")
      (node (ref "U6") (pin "41") (pinfunction "PD3_41") (pintype "passive"))
    )
    (net (code "83") (name "unconnected-(U6-PF0-OSC_IN-Pad8)") (class "Default")
      (node (ref "U6") (pin "8") (pinfunction "PF0-OSC_IN_8") (pintype "passive"))
    )
  )
)
